# projet_pcb_naked_f103.net
KiCad netlist of a schematic drawn in Altium Designer
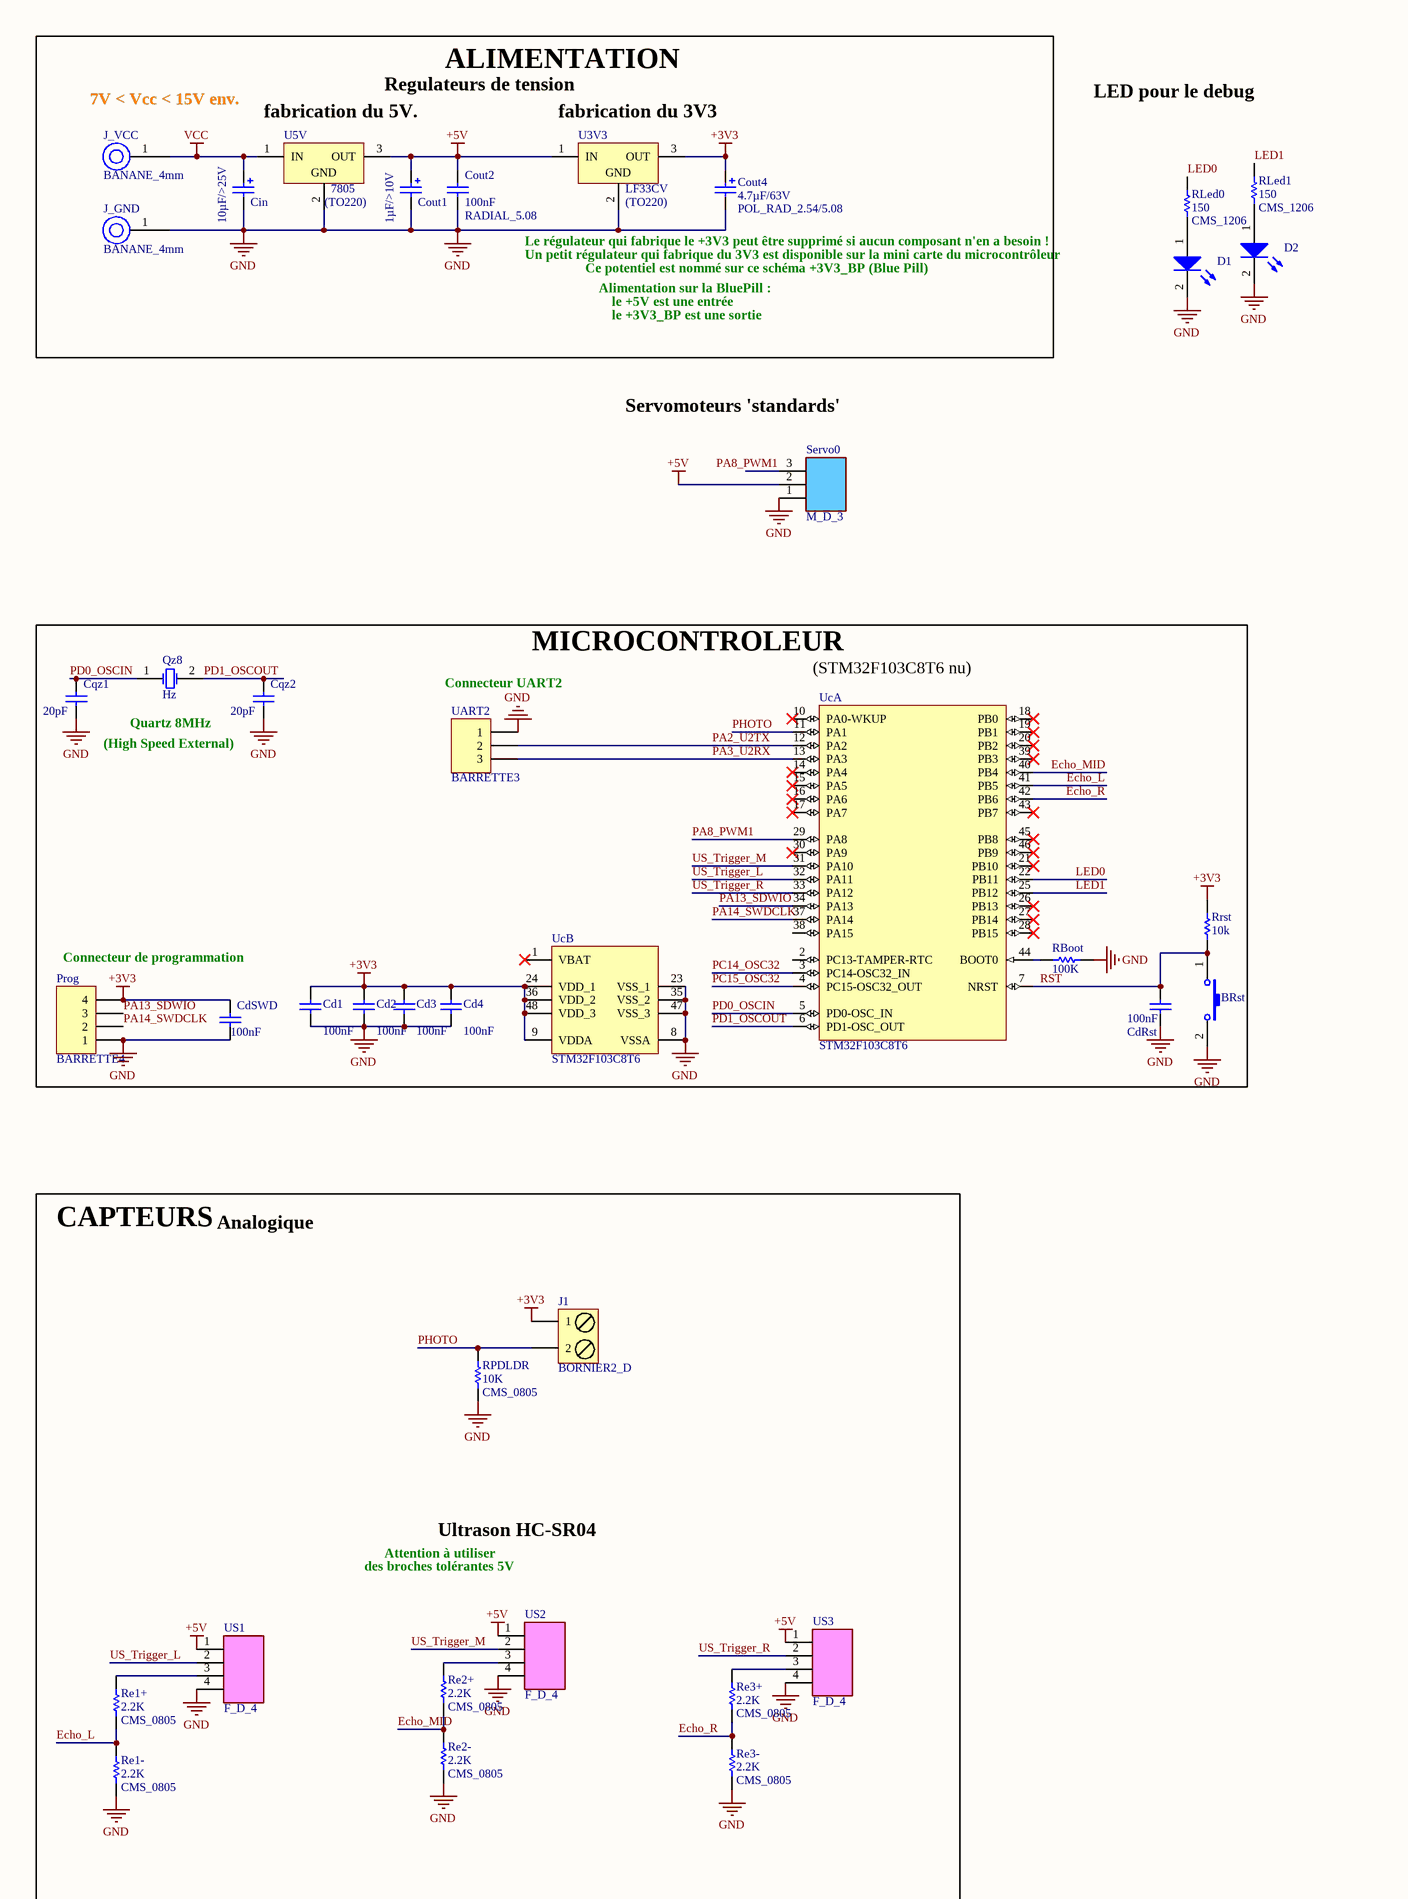
[diagram p0: projet_pcb_naked_f103.SchDoc, left]
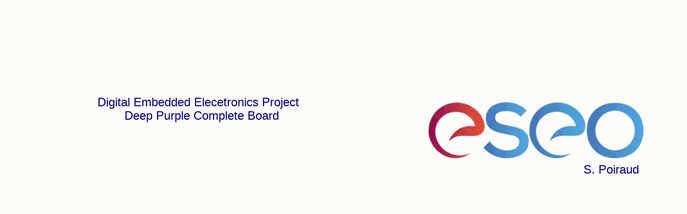
[diagram p1: projet_pcb_naked_f103.SchDoc, right]

(export (version "E")
  (design (tool "Eeschema 10.0.6"))
  (components
    (comp (ref "BRst")
      (value "BOUTON_POUSSOIR_MINIATURE_TRAVERSANT")
      (footprint "BOUTON_POUSSE_PLAT_6x6")
      (description "BOUTON POUSSOIR MINIATURE TRAVERSANT ON/OFF")
      (libsource (lib "commutation") (part "BOUTON_POUSSOIR_MINIATURE_TRAVERSANT"))
    )
    (comp (ref "Cd1")
      (value "100nF")
      (footprint "CONDENSATEUR_CMS_0805")
      (description "CONDENSATEUR CMS CERAMIQUE 0805")
      (fields (field (name "Comment") "CMS_0805"))
      (libsource (lib "composants passifs") (part "CONDENSATEUR_CMS_CER_0805"))
    )
    (comp (ref "Cd2")
      (value "100nF")
      (footprint "CONDENSATEUR_CMS_0805")
      (description "CONDENSATEUR CMS CERAMIQUE 0805")
      (fields (field (name "Comment") "CMS_0805"))
      (libsource (lib "composants passifs") (part "CONDENSATEUR_CMS_CER_0805"))
    )
    (comp (ref "Cd3")
      (value "100nF")
      (footprint "CONDENSATEUR_CMS_0805")
      (description "CONDENSATEUR CMS CERAMIQUE 0805")
      (fields (field (name "Comment") "CMS_0805"))
      (libsource (lib "composants passifs") (part "CONDENSATEUR_CMS_CER_0805"))
    )
    (comp (ref "Cd4")
      (value "100nF")
      (footprint "CONDENSATEUR_CMS_0805")
      (description "CONDENSATEUR CMS CERAMIQUE 0805")
      (fields (field (name "Comment") "CMS_0805"))
      (libsource (lib "composants passifs") (part "CONDENSATEUR_CMS_CER_0805"))
    )
    (comp (ref "CdRst")
      (value "100nF")
      (footprint "C0805_N")
      (fields (field (name "Comment") "Condensateur 0805"))
      (libsource (lib "composants passifs") (part "CONDENSATEUR_CER_RAD_5.08"))
    )
    (comp (ref "CdSWD")
      (value "100nF")
      (footprint "C0805_N")
      (fields (field (name "Comment") "Condensateur 0805"))
      (libsource (lib "composants passifs") (part "CONDENSATEUR_CER_RAD_5.08"))
    )
    (comp (ref "Cin")
      (value "10µF/>25V")
      (footprint "CONDENSATEUR_POLARISE_ELECTROLYTIQUE_RADIAL_2.0/5.08")
      (description "CONDENSATEUR POLARISE ELECTROLYTIQUE RADIAL 2.0/5.08")
      (fields (field (name "Comment") "CONDENSATEUR_POL_ELECTROLY_RAD_2.0/5.08"))
      (libsource (lib "composants passifs") (part "CONDENSATEUR_POL_ELECTROLY_RAD_2.0/5.08"))
    )
    (comp (ref "Cout1")
      (value "1µF/>10V")
      (footprint "CONDENSATEUR_POLARISE_ELECTROLYTIQUE_RADIAL_2.0/5.08")
      (description "CONDENSATEUR POLARISE ELECTROLYTIQUE RADIAL 2.0/5.08")
      (fields (field (name "Comment") "CONDENSATEUR_POL_ELECTROLY_RAD_2.0/5.08"))
      (libsource (lib "composants passifs") (part "CONDENSATEUR_POL_ELECTROLY_RAD_2.0/5.08"))
    )
    (comp (ref "Cout2")
      (value "100nF")
      (footprint "CONDENSATEUR_CERAMIQUE_RADIAL_5.08")
      (description "CONDENSATEUR TRAVERSANT CERAMIQUE RADIAL 5.08mm")
      (fields (field (name "TYPE") "RADIAL_5.08") (field (name "Comment") "CONDENSATEUR_CER_RAD_5.08"))
      (libsource (lib "composants passifs") (part "CONDENSATEUR_CER_RAD_5.08"))
    )
    (comp (ref "Cout4")
      (value "4.7µF/63V")
      (footprint "CONDENSATEUR_POLARISE_ELECTROLYTIQUE_RADIAL_2.54/5.08")
      (description "CONDENSATEUR POLARISE ELECTROLYTIQUE RADIAL 2.54/5.08")
      (fields
        (field (name "TYPE") "POL_RAD_2.54/5.08")
        (field (name "Comment") "CONDENSATEUR_POL_ELECTROLY_RAD_2.54/5.08")
      )
      (libsource (lib "composants passifs") (part "CONDENSATEUR_POL_ELECTROLY_RAD_2.54/5.08"))
    )
    (comp (ref "Cqz1")
      (value "20pF")
      (footprint "C0805_N")
      (fields (field (name "Comment") "Condensateur 0805"))
      (libsource (lib "composants passifs") (part "CONDENSATEUR_CER_RAD_5.08"))
    )
    (comp (ref "Cqz2")
      (value "20pF")
      (footprint "C0805_N")
      (fields (field (name "Comment") "Condensateur 0805"))
      (libsource (lib "composants passifs") (part "CONDENSATEUR_CER_RAD_5.08"))
    )
    (comp (ref "D1")
      (value "LED_CMS_0805")
      (footprint "LED_CMS_0805")
      (description "LED CMS 0805")
      (libsource (lib "affichage") (part "LED_CMS_0805"))
    )
    (comp (ref "D2")
      (value "LED_CMS_0805")
      (footprint "LED_CMS_0805")
      (description "LED CMS 0805")
      (libsource (lib "affichage") (part "LED_CMS_0805"))
    )
    (comp (ref "J1")
      (value "BORNIER2 DROIT A VIS")
      (footprint "BORNIER2_A_VIS")
      (description "BORNIER 2 PLOTS DROIT A VIS 5.08mm")
      (fields (field (name "TYPE") "BORNIER2_D"))
      (libsource (lib "connecteurs") (part "BORNIER2_DROIT_A VIS"))
    )
    (comp (ref "J_GND")
      (value "DOUILLE BANANE 4mm")
      (footprint "DOUILLE_BANANE_4mm")
      (description "DOUILLE BANANE 4 mm")
      (fields (field (name "TYPE") "BANANE_4mm"))
      (libsource (lib "connecteurs") (part "DOUILLE_BANANE_4mm"))
    )
    (comp (ref "J_VCC")
      (value "DOUILLE BANANE 4mm")
      (footprint "DOUILLE_BANANE_4mm")
      (description "DOUILLE BANANE 4 mm")
      (fields (field (name "TYPE") "BANANE_4mm"))
      (libsource (lib "connecteurs") (part "DOUILLE_BANANE_4mm"))
    )
    (comp (ref "Prog")
      (value "BARRETTE4")
      (footprint "HE14_4")
      (description "Header, 4-Pin")
      (fields (field (name "PUBLISHER") "Altium Limited"))
      (libsource (lib "Connecteur") (part "BARRETTE4"))
    )
    (comp (ref "Qz8")
      (value "Hz")
      (footprint "HC49/4H_SMX")
      (description "Crystal Oscillator")
      (fields (field (name "PUBLISHER") "Altium Limited"))
      (libsource (lib "_ROBOT") (part "Quartz"))
    )
    (comp (ref "RBoot")
      (value "100K")
      (footprint "RESISTANCE_CMS_0805")
      (description "RESISTANCE CMS 0805")
      (fields (field (name "Comment") "RESISTANCE_CMS_0805"))
      (libsource (lib "composants passifs") (part "RESISTANCE_CMS_0805"))
    )
    (comp (ref "Re1+")
      (value "2.2K")
      (footprint "RESISTANCE_CMS_0805")
      (description "RESISTANCE CMS 0805")
      (fields (field (name "TYPE") "CMS_0805") (field (name "Comment") "RESISTANCE_CMS_0805"))
      (libsource (lib "composants passifs") (part "RESISTANCE_CMS_0805"))
    )
    (comp (ref "Re1-")
      (value "2.2K")
      (footprint "RESISTANCE_CMS_0805")
      (description "RESISTANCE CMS 0805")
      (fields (field (name "TYPE") "CMS_0805") (field (name "Comment") "RESISTANCE_CMS_0805"))
      (libsource (lib "composants passifs") (part "RESISTANCE_CMS_0805"))
    )
    (comp (ref "Re2+")
      (value "2.2K")
      (footprint "RESISTANCE_CMS_0805")
      (description "RESISTANCE CMS 0805")
      (fields (field (name "TYPE") "CMS_0805") (field (name "Comment") "RESISTANCE_CMS_0805"))
      (libsource (lib "composants passifs") (part "RESISTANCE_CMS_0805"))
    )
    (comp (ref "Re2-")
      (value "2.2K")
      (footprint "RESISTANCE_CMS_0805")
      (description "RESISTANCE CMS 0805")
      (fields (field (name "TYPE") "CMS_0805") (field (name "Comment") "RESISTANCE_CMS_0805"))
      (libsource (lib "composants passifs") (part "RESISTANCE_CMS_0805"))
    )
    (comp (ref "Re3+")
      (value "2.2K")
      (footprint "RESISTANCE_CMS_0805")
      (description "RESISTANCE CMS 0805")
      (fields (field (name "TYPE") "CMS_0805") (field (name "Comment") "RESISTANCE_CMS_0805"))
      (libsource (lib "composants passifs") (part "RESISTANCE_CMS_0805"))
    )
    (comp (ref "Re3-")
      (value "2.2K")
      (footprint "RESISTANCE_CMS_0805")
      (description "RESISTANCE CMS 0805")
      (fields (field (name "TYPE") "CMS_0805") (field (name "Comment") "RESISTANCE_CMS_0805"))
      (libsource (lib "composants passifs") (part "RESISTANCE_CMS_0805"))
    )
    (comp (ref "RLed0")
      (value "150")
      (footprint "RESISTANCE_CMS_1206")
      (description "RESISTANCE CMS 1206")
      (fields (field (name "TYPE") "CMS_1206") (field (name "Comment") "RESISTANCE_CMS_1206"))
      (libsource (lib "composants passifs") (part "RESISTANCE_CMS_1206"))
    )
    (comp (ref "RLed1")
      (value "150")
      (footprint "RESISTANCE_CMS_1206")
      (description "RESISTANCE CMS 1206")
      (fields (field (name "TYPE") "CMS_1206") (field (name "Comment") "RESISTANCE_CMS_1206"))
      (libsource (lib "composants passifs") (part "RESISTANCE_CMS_1206"))
    )
    (comp (ref "RPDLDR")
      (value "10K")
      (footprint "RESISTANCE_CMS_0805")
      (description "RESISTANCE CMS 0805")
      (fields (field (name "TYPE") "CMS_0805") (field (name "Comment") "RESISTANCE_CMS_0805"))
      (libsource (lib "composants passifs") (part "RESISTANCE_CMS_0805"))
    )
    (comp (ref "Rrst")
      (value "10k")
      (footprint "R1206_N")
      (description "Resistor")
      (fields (field (name "PUBLISHER") "Altium Limited"))
      (libsource (lib "_ROBOT") (part "Resistor"))
    )
    (comp (ref "Servo0")
      (value "BARRETTE 3 CONTACTS 1 RANGEE MALE DROITE")
      (footprint "BARRETTE_3_M_D")
      (fields (field (name "TYPE") "M_D_3"))
      (libsource (lib "connecteurs") (part "BARRETTE_3 CONTACTS_1 RANGEE_MALE_DROITE"))
    )
    (comp (ref "U3V3")
      (value "REGULATEUR_TO220_78XX")
      (footprint "REGULATEUR_TO220_78XX")
      (description "REGULATEUR DE TENSION POSITIVE 78XX BOITIER TO220")
      (fields (field (name "TYPE") "LF33CV") (field (name "PACKAGE") "(TO220)"))
      (libsource (lib "composants actifs") (part "REGULATEUR_TO220_78XX"))
    )
    (comp (ref "U5V")
      (value "REGULATEUR_TO220_78XX")
      (footprint "REGULATEUR_TO220_78XX")
      (description "REGULATEUR DE TENSION POSITIVE 78XX BOITIER TO220")
      (fields (field (name "TYPE") "7805") (field (name "PACKAGE") "(TO220)"))
      (libsource (lib "composants actifs") (part "REGULATEUR_TO220_78XX"))
    )
    (comp (ref "UART2")
      (value "BARRETTE3")
      (footprint "HDR1X3")
      (description "Header, 3-Pin")
      (fields (field (name "PUBLISHER") "Altium Limited"))
      (libsource (lib "Connecteur") (part "BARRETTE3"))
    )
    (comp (ref "Uc")
      (value "STM32F103C8T6")
      (footprint "STM-LQFP48_N")
      (libsource (lib "STMicroelectronics STM32 F1") (part "STM32F103C8T6"))
    )
    (comp (ref "US1")
      (value "BARRETTE_4 CONTACTS_1 RANGEE_FEMELLE_DROITE")
      (footprint "BARRETTE_4_F_D")
      (description "BARRETTE 4 CONTACTS 1 RANGEE FEMELLE DROITE")
      (fields (field (name "TYPE") "F_D_4"))
      (libsource (lib "connecteurs") (part "BARRETTE_4 CONTACTS_1 RANGEE_FEMELLE_DROITE"))
    )
    (comp (ref "US2")
      (value "BARRETTE_4 CONTACTS_1 RANGEE_FEMELLE_DROITE")
      (footprint "BARRETTE_4_F_D")
      (description "BARRETTE 4 CONTACTS 1 RANGEE FEMELLE DROITE")
      (fields (field (name "TYPE") "F_D_4"))
      (libsource (lib "connecteurs") (part "BARRETTE_4 CONTACTS_1 RANGEE_FEMELLE_DROITE"))
    )
    (comp (ref "US3")
      (value "BARRETTE_4 CONTACTS_1 RANGEE_FEMELLE_DROITE")
      (footprint "BARRETTE_4_F_D")
      (description "BARRETTE 4 CONTACTS 1 RANGEE FEMELLE DROITE")
      (fields (field (name "TYPE") "F_D_4"))
      (libsource (lib "connecteurs") (part "BARRETTE_4 CONTACTS_1 RANGEE_FEMELLE_DROITE"))
    )
  )
  (nets
    (net (code "1") (name "+3V3") (class "Default")
      (node (ref "Cd1") (pin "2") (pinfunction "2_2") (pintype "passive"))
      (node (ref "Cd2") (pin "2") (pinfunction "2_2") (pintype "passive"))
      (node (ref "Cd3") (pin "2") (pinfunction "2_2") (pintype "passive"))
      (node (ref "Cd4") (pin "2") (pinfunction "2_2") (pintype "passive"))
      (node (ref "CdSWD") (pin "2") (pinfunction "2_2") (pintype "passive"))
      (node (ref "Cout4") (pin "1") (pinfunction "1_1") (pintype "passive"))
      (node (ref "J1") (pin "1") (pinfunction "1_1") (pintype "passive"))
      (node (ref "Prog") (pin "4") (pinfunction "4_4") (pintype "passive"))
      (node (ref "Rrst") (pin "1") (pinfunction "1_1") (pintype "passive"))
      (node (ref "U3V3") (pin "3") (pinfunction "OUT_3") (pintype "power_in"))
      (node (ref "Uc") (pin "24") (pinfunction "VDD_1_24") (pintype "power_in"))
      (node (ref "Uc") (pin "36") (pinfunction "VDD_2_36") (pintype "power_in"))
      (node (ref "Uc") (pin "48") (pinfunction "VDD_3_48") (pintype "power_in"))
      (node (ref "Uc") (pin "9") (pinfunction "VDDA_9") (pintype "power_in"))
    )
    (net (code "2") (name "+5V") (class "Default")
      (node (ref "Cout1") (pin "1") (pinfunction "1_1") (pintype "passive"))
      (node (ref "Cout2") (pin "2") (pinfunction "2_2") (pintype "passive"))
      (node (ref "Servo0") (pin "2") (pinfunction "2_2") (pintype "passive"))
      (node (ref "U3V3") (pin "1") (pinfunction "IN_1") (pintype "power_in"))
      (node (ref "U5V") (pin "3") (pinfunction "OUT_3") (pintype "power_in"))
      (node (ref "US1") (pin "1") (pinfunction "1_1") (pintype "passive"))
      (node (ref "US2") (pin "1") (pinfunction "1_1") (pintype "passive"))
      (node (ref "US3") (pin "1") (pinfunction "1_1") (pintype "passive"))
    )
    (net (code "3") (name "/Echo_L") (class "Default")
      (node (ref "Re1+") (pin "1") (pinfunction "1_1") (pintype "passive"))
      (node (ref "Re1-") (pin "2") (pinfunction "2_2") (pintype "passive"))
      (node (ref "Uc") (pin "41") (pinfunction "PB5_41") (pintype "bidirectional"))
    )
    (net (code "4") (name "/Echo_MID") (class "Default")
      (node (ref "Re2+") (pin "1") (pinfunction "1_1") (pintype "passive"))
      (node (ref "Re2-") (pin "2") (pinfunction "2_2") (pintype "passive"))
      (node (ref "Uc") (pin "40") (pinfunction "PB4_40") (pintype "bidirectional"))
    )
    (net (code "5") (name "/Echo_R") (class "Default")
      (node (ref "Re3+") (pin "1") (pinfunction "1_1") (pintype "passive"))
      (node (ref "Re3-") (pin "2") (pinfunction "2_2") (pintype "passive"))
      (node (ref "Uc") (pin "42") (pinfunction "PB6_42") (pintype "bidirectional"))
    )
    (net (code "6") (name "/LED0") (class "Default")
      (node (ref "RLed0") (pin "2") (pinfunction "2_2") (pintype "passive"))
      (node (ref "Uc") (pin "22") (pinfunction "PB11_22") (pintype "bidirectional"))
    )
    (net (code "7") (name "/LED1") (class "Default")
      (node (ref "RLed1") (pin "2") (pinfunction "2_2") (pintype "passive"))
      (node (ref "Uc") (pin "25") (pinfunction "PB12_25") (pintype "bidirectional"))
    )
    (net (code "8") (name "/PA2_U2TX") (class "Default")
      (node (ref "UART2") (pin "2") (pinfunction "2_2") (pintype "passive"))
      (node (ref "Uc") (pin "12") (pinfunction "PA2_12") (pintype "bidirectional"))
    )
    (net (code "9") (name "/PA3_U2RX") (class "Default")
      (node (ref "UART2") (pin "3") (pinfunction "3_3") (pintype "passive"))
      (node (ref "Uc") (pin "13") (pinfunction "PA3_13") (pintype "bidirectional"))
    )
    (net (code "10") (name "/PA8_PWM1") (class "Default")
      (node (ref "Servo0") (pin "3") (pinfunction "3_3") (pintype "passive"))
      (node (ref "Uc") (pin "29") (pinfunction "PA8_29") (pintype "bidirectional"))
    )
    (net (code "11") (name "/PA13_SDWIO") (class "Default")
      (node (ref "Prog") (pin "3") (pinfunction "3_3") (pintype "passive"))
      (node (ref "Uc") (pin "34") (pinfunction "PA13_34") (pintype "bidirectional"))
    )
    (net (code "12") (name "/PA14_SWDCLK") (class "Default")
      (node (ref "Prog") (pin "2") (pinfunction "2_2") (pintype "passive"))
      (node (ref "Uc") (pin "37") (pinfunction "PA14_37") (pintype "bidirectional"))
    )
    (net (code "13") (name "/PC14_OSC32") (class "Default")
      (node (ref "Uc") (pin "3") (pinfunction "PC14-OSC32_IN_3") (pintype "bidirectional"))
    )
    (net (code "14") (name "/PC15_OSC32") (class "Default")
      (node (ref "Uc") (pin "4") (pinfunction "PC15-OSC32_OUT_4") (pintype "bidirectional"))
    )
    (net (code "15") (name "/PD0_OSCIN") (class "Default")
      (node (ref "Cqz1") (pin "2") (pinfunction "2_2") (pintype "passive"))
      (node (ref "Qz8") (pin "1") (pinfunction "OSC1_1") (pintype "passive"))
      (node (ref "Uc") (pin "5") (pinfunction "PD0-OSC_IN_5") (pintype "bidirectional"))
    )
    (net (code "16") (name "/PD1_OSCOUT") (class "Default")
      (node (ref "Cqz2") (pin "2") (pinfunction "2_2") (pintype "passive"))
      (node (ref "Qz8") (pin "2") (pinfunction "OSC2_2") (pintype "passive"))
      (node (ref "Uc") (pin "6") (pinfunction "PD1-OSC_OUT_6") (pintype "bidirectional"))
    )
    (net (code "17") (name "/PHOTO") (class "Default")
      (node (ref "J1") (pin "2") (pinfunction "2_2") (pintype "passive"))
      (node (ref "RPDLDR") (pin "2") (pinfunction "2_2") (pintype "passive"))
      (node (ref "Uc") (pin "11") (pinfunction "PA1_11") (pintype "bidirectional"))
    )
    (net (code "18") (name "/RST") (class "Default")
      (node (ref "BRst") (pin "1") (pinfunction "1_1") (pintype "passive"))
      (node (ref "CdRst") (pin "2") (pinfunction "2_2") (pintype "passive"))
      (node (ref "Rrst") (pin "2") (pinfunction "2_2") (pintype "passive"))
      (node (ref "Uc") (pin "7") (pinfunction "NRST_7") (pintype "bidirectional"))
    )
    (net (code "19") (name "/US_Trigger_L") (class "Default")
      (node (ref "US1") (pin "2") (pinfunction "2_2") (pintype "passive"))
      (node (ref "Uc") (pin "32") (pinfunction "PA11_32") (pintype "bidirectional"))
    )
    (net (code "20") (name "/US_Trigger_M") (class "Default")
      (node (ref "US2") (pin "2") (pinfunction "2_2") (pintype "passive"))
      (node (ref "Uc") (pin "31") (pinfunction "PA10_31") (pintype "bidirectional"))
    )
    (net (code "21") (name "/US_Trigger_R") (class "Default")
      (node (ref "US3") (pin "2") (pinfunction "2_2") (pintype "passive"))
      (node (ref "Uc") (pin "33") (pinfunction "PA12_33") (pintype "bidirectional"))
    )
    (net (code "22") (name "GND") (class "Default")
      (node (ref "BRst") (pin "2") (pinfunction "2_2") (pintype "passive"))
      (node (ref "Cd1") (pin "1") (pinfunction "1_1") (pintype "passive"))
      (node (ref "Cd2") (pin "1") (pinfunction "1_1") (pintype "passive"))
      (node (ref "Cd3") (pin "1") (pinfunction "1_1") (pintype "passive"))
      (node (ref "Cd4") (pin "1") (pinfunction "1_1") (pintype "passive"))
      (node (ref "CdRst") (pin "1") (pinfunction "1_1") (pintype "passive"))
      (node (ref "CdSWD") (pin "1") (pinfunction "1_1") (pintype "passive"))
      (node (ref "Cin") (pin "2") (pinfunction "2_2") (pintype "passive"))
      (node (ref "Cout1") (pin "2") (pinfunction "2_2") (pintype "passive"))
      (node (ref "Cout2") (pin "1") (pinfunction "1_1") (pintype "passive"))
      (node (ref "Cout4") (pin "2") (pinfunction "2_2") (pintype "passive"))
      (node (ref "Cqz1") (pin "1") (pinfunction "1_1") (pintype "passive"))
      (node (ref "Cqz2") (pin "1") (pinfunction "1_1") (pintype "passive"))
      (node (ref "D1") (pin "2") (pinfunction "2_2") (pintype "passive"))
      (node (ref "D2") (pin "2") (pinfunction "2_2") (pintype "passive"))
      (node (ref "J_GND") (pin "1") (pinfunction "1_1") (pintype "passive"))
      (node (ref "Prog") (pin "1") (pinfunction "1_1") (pintype "passive"))
      (node (ref "RBoot") (pin "1") (pinfunction "1_1") (pintype "passive"))
      (node (ref "RPDLDR") (pin "1") (pinfunction "1_1") (pintype "passive"))
      (node (ref "Re1-") (pin "1") (pinfunction "1_1") (pintype "passive"))
      (node (ref "Re2-") (pin "1") (pinfunction "1_1") (pintype "passive"))
      (node (ref "Re3-") (pin "1") (pinfunction "1_1") (pintype "passive"))
      (node (ref "Servo0") (pin "1") (pinfunction "1_1") (pintype "passive"))
      (node (ref "U3V3") (pin "2") (pinfunction "GND_2") (pintype "power_in"))
      (node (ref "U5V") (pin "2") (pinfunction "GND_2") (pintype "power_in"))
      (node (ref "UART2") (pin "1") (pinfunction "1_1") (pintype "passive"))
      (node (ref "US1") (pin "4") (pinfunction "4_4") (pintype "passive"))
      (node (ref "US2") (pin "4") (pinfunction "4_4") (pintype "passive"))
      (node (ref "US3") (pin "4") (pinfunction "4_4") (pintype "passive"))
      (node (ref "Uc") (pin "23") (pinfunction "VSS_1_23") (pintype "power_in"))
      (node (ref "Uc") (pin "35") (pinfunction "VSS_2_35") (pintype "power_in"))
      (node (ref "Uc") (pin "47") (pinfunction "VSS_3_47") (pintype "power_in"))
      (node (ref "Uc") (pin "8") (pinfunction "VSSA_8") (pintype "power_in"))
    )
    (net (code "23") (name "Net-(D1-Pad1)") (class "Default")
      (node (ref "D1") (pin "1") (pinfunction "1_1") (pintype "passive"))
      (node (ref "RLed0") (pin "1") (pinfunction "1_1") (pintype "passive"))
    )
    (net (code "24") (name "Net-(D2-Pad1)") (class "Default")
      (node (ref "D2") (pin "1") (pinfunction "1_1") (pintype "passive"))
      (node (ref "RLed1") (pin "1") (pinfunction "1_1") (pintype "passive"))
    )
    (net (code "25") (name "Net-(Re1+-Pad2)") (class "Default")
      (node (ref "Re1+") (pin "2") (pinfunction "2_2") (pintype "passive"))
      (node (ref "US1") (pin "3") (pinfunction "3_3") (pintype "passive"))
    )
    (net (code "26") (name "Net-(Re2+-Pad2)") (class "Default")
      (node (ref "Re2+") (pin "2") (pinfunction "2_2") (pintype "passive"))
      (node (ref "US2") (pin "3") (pinfunction "3_3") (pintype "passive"))
    )
    (net (code "27") (name "Net-(Re3+-Pad2)") (class "Default")
      (node (ref "Re3+") (pin "2") (pinfunction "2_2") (pintype "passive"))
      (node (ref "US3") (pin "3") (pinfunction "3_3") (pintype "passive"))
    )
    (net (code "28") (name "Net-(UcA-BOOT0)") (class "Default")
      (node (ref "RBoot") (pin "2") (pinfunction "2_2") (pintype "passive"))
      (node (ref "Uc") (pin "44") (pinfunction "BOOT0_44") (pintype "input"))
    )
    (net (code "29") (name "VCC") (class "Default")
      (node (ref "Cin") (pin "1") (pinfunction "1_1") (pintype "passive"))
      (node (ref "J_VCC") (pin "1") (pinfunction "1_1") (pintype "passive"))
      (node (ref "U5V") (pin "1") (pinfunction "IN_1") (pintype "power_in"))
    )
    (net (code "30") (name "unconnected-(UcA-PA0-WKUP-Pad10)") (class "Default")
      (node (ref "Uc") (pin "10") (pinfunction "PA0-WKUP_10") (pintype "bidirectional+no_connect"))
    )
    (net (code "31") (name "unconnected-(UcA-PA4-Pad14)") (class "Default")
      (node (ref "Uc") (pin "14") (pinfunction "PA4_14") (pintype "bidirectional+no_connect"))
    )
    (net (code "32") (name "unconnected-(UcA-PA5-Pad15)") (class "Default")
      (node (ref "Uc") (pin "15") (pinfunction "PA5_15") (pintype "bidirectional+no_connect"))
    )
    (net (code "33") (name "unconnected-(UcA-PA6-Pad16)") (class "Default")
      (node (ref "Uc") (pin "16") (pinfunction "PA6_16") (pintype "bidirectional+no_connect"))
    )
    (net (code "34") (name "unconnected-(UcA-PA7-Pad17)") (class "Default")
      (node (ref "Uc") (pin "17") (pinfunction "PA7_17") (pintype "bidirectional+no_connect"))
    )
    (net (code "35") (name "unconnected-(UcA-PA9-Pad30)") (class "Default")
      (node (ref "Uc") (pin "30") (pinfunction "PA9_30") (pintype "bidirectional+no_connect"))
    )
    (net (code "36") (name "unconnected-(UcA-PA15-Pad38)") (class "Default")
      (node (ref "Uc") (pin "38") (pinfunction "PA15_38") (pintype "bidirectional"))
    )
    (net (code "37") (name "unconnected-(UcA-PB0-Pad18)") (class "Default")
      (node (ref "Uc") (pin "18") (pinfunction "PB0_18") (pintype "bidirectional+no_connect"))
    )
    (net (code "38") (name "unconnected-(UcA-PB1-Pad19)") (class "Default")
      (node (ref "Uc") (pin "19") (pinfunction "PB1_19") (pintype "bidirectional+no_connect"))
    )
    (net (code "39") (name "unconnected-(UcA-PB2-Pad20)") (class "Default")
      (node (ref "Uc") (pin "20") (pinfunction "PB2_20") (pintype "bidirectional+no_connect"))
    )
    (net (code "40") (name "unconnected-(UcA-PB3-Pad39)") (class "Default")
      (node (ref "Uc") (pin "39") (pinfunction "PB3_39") (pintype "bidirectional+no_connect"))
    )
    (net (code "41") (name "unconnected-(UcA-PB7-Pad43)") (class "Default")
      (node (ref "Uc") (pin "43") (pinfunction "PB7_43") (pintype "bidirectional+no_connect"))
    )
    (net (code "42") (name "unconnected-(UcA-PB8-Pad45)") (class "Default")
      (node (ref "Uc") (pin "45") (pinfunction "PB8_45") (pintype "bidirectional+no_connect"))
    )
    (net (code "43") (name "unconnected-(UcA-PB9-Pad46)") (class "Default")
      (node (ref "Uc") (pin "46") (pinfunction "PB9_46") (pintype "bidirectional+no_connect"))
    )
    (net (code "44") (name "unconnected-(UcA-PB10-Pad21)") (class "Default")
      (node (ref "Uc") (pin "21") (pinfunction "PB10_21") (pintype "bidirectional+no_connect"))
    )
    (net (code "45") (name "unconnected-(UcA-PB13-Pad26)") (class "Default")
      (node (ref "Uc") (pin "26") (pinfunction "PB13_26") (pintype "bidirectional+no_connect"))
    )
    (net (code "46") (name "unconnected-(UcA-PB14-Pad27)") (class "Default")
      (node (ref "Uc") (pin "27") (pinfunction "PB14_27") (pintype "bidirectional+no_connect"))
    )
    (net (code "47") (name "unconnected-(UcA-PB15-Pad28)") (class "Default")
      (node (ref "Uc") (pin "28") (pinfunction "PB15_28") (pintype "bidirectional+no_connect"))
    )
    (net (code "48") (name "unconnected-(UcA-PC13-TAMPER-RTC-Pad2)") (class "Default")
      (node (ref "Uc") (pin "2") (pinfunction "PC13-TAMPER-RTC_2") (pintype "bidirectional"))
    )
    (net (code "49") (name "unconnected-(UcB-VBAT-Pad1)") (class "Default")
      (node (ref "Uc") (pin "1") (pinfunction "VBAT_1") (pintype "power_in+no_connect"))
    )
  )
)
